# Probe-Scope_ADC_v1_0.net
KiCad netlist of a schematic drawn in Altium Designer
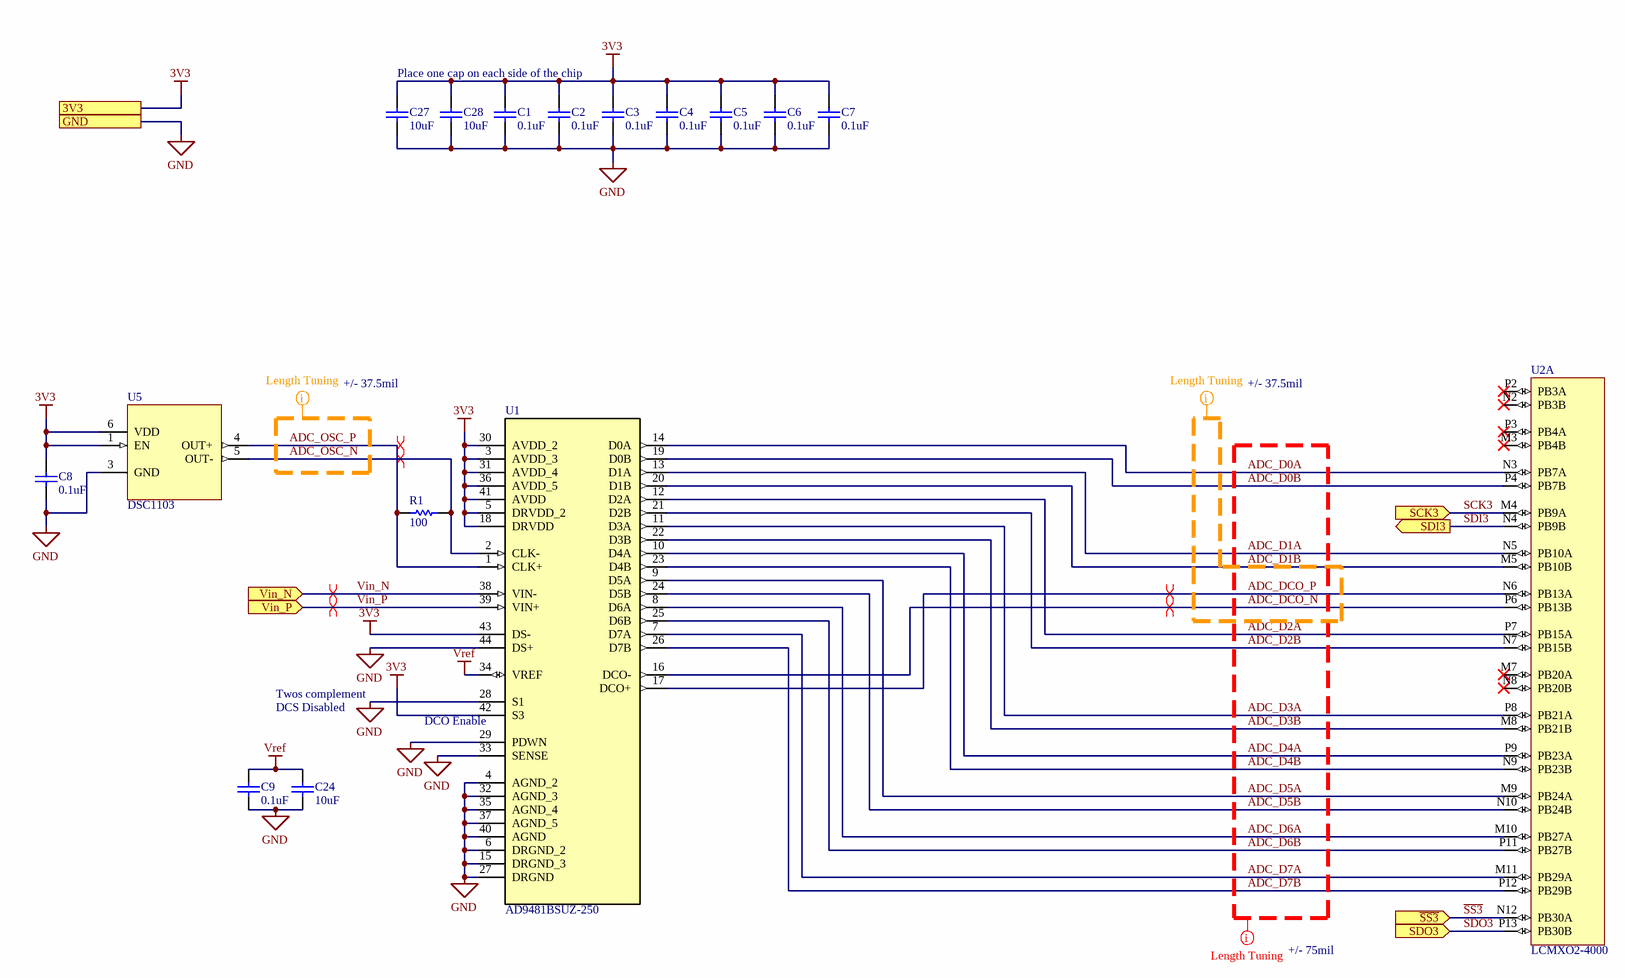
[diagram p0: Probe-Scope ADC v1.0.SchDoc]

(export (version "E")
  (design (tool "Eeschema 10.0.6"))
  (components
    (comp (ref "C1")
      (value "0.1uF")
      (footprint "0402(1005)")
      (fields
        (field (name "MANF") "Samsung Electro-Mechanics")
        (field (name "TOLERANCE") "10")
        (field (name "VOLTAGE") "6.3")
        (field (name "MODIFIED BY") "jrowley")
        (field (name "APPROVED") "False")
      )
      (libsource (lib "MENG Database Library VPN") (part "Cap"))
    )
    (comp (ref "C2")
      (value "0.1uF")
      (footprint "0402(1005)")
      (fields
        (field (name "MANF") "Samsung Electro-Mechanics")
        (field (name "TOLERANCE") "10")
        (field (name "VOLTAGE") "6.3")
        (field (name "MODIFIED BY") "jrowley")
        (field (name "APPROVED") "False")
      )
      (libsource (lib "MENG Database Library VPN") (part "Cap"))
    )
    (comp (ref "C3")
      (value "0.1uF")
      (footprint "0402(1005)")
      (fields
        (field (name "MANF") "Samsung Electro-Mechanics")
        (field (name "TOLERANCE") "10")
        (field (name "VOLTAGE") "6.3")
        (field (name "MODIFIED BY") "jrowley")
        (field (name "APPROVED") "False")
      )
      (libsource (lib "MENG Database Library VPN") (part "Cap"))
    )
    (comp (ref "C4")
      (value "0.1uF")
      (footprint "0402(1005)")
      (fields
        (field (name "MANF") "Samsung Electro-Mechanics")
        (field (name "TOLERANCE") "10")
        (field (name "VOLTAGE") "6.3")
        (field (name "MODIFIED BY") "jrowley")
        (field (name "APPROVED") "False")
      )
      (libsource (lib "MENG Database Library VPN") (part "Cap"))
    )
    (comp (ref "C5")
      (value "0.1uF")
      (footprint "0402(1005)")
      (fields
        (field (name "MANF") "Samsung Electro-Mechanics")
        (field (name "TOLERANCE") "10")
        (field (name "VOLTAGE") "6.3")
        (field (name "MODIFIED BY") "jrowley")
        (field (name "APPROVED") "False")
      )
      (libsource (lib "MENG Database Library VPN") (part "Cap"))
    )
    (comp (ref "C6")
      (value "0.1uF")
      (footprint "0402(1005)")
      (fields
        (field (name "MANF") "Samsung Electro-Mechanics")
        (field (name "TOLERANCE") "10")
        (field (name "VOLTAGE") "6.3")
        (field (name "MODIFIED BY") "jrowley")
        (field (name "APPROVED") "False")
      )
      (libsource (lib "MENG Database Library VPN") (part "Cap"))
    )
    (comp (ref "C7")
      (value "0.1uF")
      (footprint "0402(1005)")
      (fields
        (field (name "MANF") "Samsung Electro-Mechanics")
        (field (name "TOLERANCE") "10")
        (field (name "VOLTAGE") "6.3")
        (field (name "MODIFIED BY") "jrowley")
        (field (name "APPROVED") "False")
      )
      (libsource (lib "MENG Database Library VPN") (part "Cap"))
    )
    (comp (ref "C8")
      (value "0.1uF")
      (footprint "0402(1005)")
      (fields
        (field (name "MANF") "Samsung Electro-Mechanics")
        (field (name "TOLERANCE") "10")
        (field (name "VOLTAGE") "6.3")
        (field (name "MODIFIED BY") "jrowley")
        (field (name "APPROVED") "False")
      )
      (libsource (lib "MENG Database Library VPN") (part "Cap"))
    )
    (comp (ref "C9")
      (value "0.1uF")
      (footprint "0402(1005)")
      (fields
        (field (name "MANF") "Samsung Electro-Mechanics")
        (field (name "TOLERANCE") "10")
        (field (name "VOLTAGE") "6.3")
        (field (name "MODIFIED BY") "jrowley")
        (field (name "APPROVED") "False")
      )
      (libsource (lib "MENG Database Library VPN") (part "Cap"))
    )
    (comp (ref "C24")
      (value "10uF")
      (footprint "0603(1608)")
      (fields
        (field (name "MANF") "Samsung Electro-Mechanics")
        (field (name "TOLERANCE") "20")
        (field (name "VOLTAGE") "25")
        (field (name "MODIFIED BY") "sotterbacher")
        (field (name "APPROVED") "True")
      )
      (libsource (lib "MENG Database Library VPN") (part "Cap"))
    )
    (comp (ref "C27")
      (value "10uF")
      (footprint "0603(1608)")
      (fields
        (field (name "MANF") "Samsung Electro-Mechanics")
        (field (name "TOLERANCE") "20")
        (field (name "VOLTAGE") "25")
        (field (name "MODIFIED BY") "sotterbacher")
        (field (name "APPROVED") "True")
      )
      (libsource (lib "MENG Database Library VPN") (part "Cap"))
    )
    (comp (ref "C28")
      (value "10uF")
      (footprint "0603(1608)")
      (fields
        (field (name "MANF") "Samsung Electro-Mechanics")
        (field (name "TOLERANCE") "20")
        (field (name "VOLTAGE") "25")
        (field (name "MODIFIED BY") "sotterbacher")
        (field (name "APPROVED") "True")
      )
      (libsource (lib "MENG Database Library VPN") (part "Cap"))
    )
    (comp (ref "R1")
      (value "100")
      (footprint "0402(1005)")
      (fields
        (field (name "MANF") "Yageo")
        (field (name "TOLERANCE") "1")
        (field (name "POWER") "0.0625")
        (field (name "MODIFIED BY") "jrowley")
        (field (name "APPROVED") "False")
      )
      (libsource (lib "MENG Database Library VPN") (part "Res1"))
    )
    (comp (ref "U1")
      (value "AD9481BSUZ-250")
      (footprint "QFP80P1200X1200X120-44N")
      (description "Single ADC Pipelined 250Msps 8-bit Parallel/LVDS 44-Pin TQFP Tray")
      (fields (field (name "MANF") "Analog Devices Inc."))
      (libsource (lib "PS") (part "AD9481BSUZ-250"))
    )
    (comp (ref "U2")
      (value "LCMXO2-4000")
      (footprint "132_Ball_csBGA_MachXO2")
      (fields (field (name "MANF") "Lattice Semiconductor"))
      (libsource (lib "PS v1.0") (part "MachXO2-4000"))
    )
    (comp (ref "U5")
      (value "DSC1103")
      (footprint "MCHP_H5A")
      (fields (field (name "MANF") "Microchip Technology"))
      (libsource (lib "PS v1.0") (part "DSC1103"))
    )
  )
  (nets
    (net (code "1") (name "/ADC_D0A") (class "Default")
      (node (ref "U1") (pin "14") (pinfunction "D0A_14") (pintype "output"))
      (node (ref "U2") (pin "N3") (pinfunction "PB7A_N3") (pintype "bidirectional"))
    )
    (net (code "2") (name "/ADC_D0B") (class "Default")
      (node (ref "U1") (pin "19") (pinfunction "D0B_19") (pintype "output"))
      (node (ref "U2") (pin "P4") (pinfunction "PB7B_P4") (pintype "bidirectional"))
    )
    (net (code "3") (name "/ADC_D1A") (class "Default")
      (node (ref "U1") (pin "13") (pinfunction "D1A_13") (pintype "output"))
      (node (ref "U2") (pin "N5") (pinfunction "PB10A_N5") (pintype "bidirectional"))
    )
    (net (code "4") (name "/ADC_D1B") (class "Default")
      (node (ref "U1") (pin "20") (pinfunction "D1B_20") (pintype "output"))
      (node (ref "U2") (pin "M5") (pinfunction "PB10B_M5") (pintype "bidirectional"))
    )
    (net (code "5") (name "/ADC_D2A") (class "Default")
      (node (ref "U1") (pin "12") (pinfunction "D2A_12") (pintype "output"))
      (node (ref "U2") (pin "P7") (pinfunction "PB15A_P7") (pintype "bidirectional"))
    )
    (net (code "6") (name "/ADC_D2B") (class "Default")
      (node (ref "U1") (pin "21") (pinfunction "D2B_21") (pintype "output"))
      (node (ref "U2") (pin "N7") (pinfunction "PB15B_N7") (pintype "bidirectional"))
    )
    (net (code "7") (name "/ADC_D3A") (class "Default")
      (node (ref "U1") (pin "11") (pinfunction "D3A_11") (pintype "output"))
      (node (ref "U2") (pin "P8") (pinfunction "PB21A_P8") (pintype "bidirectional"))
    )
    (net (code "8") (name "/ADC_D3B") (class "Default")
      (node (ref "U1") (pin "22") (pinfunction "D3B_22") (pintype "output"))
      (node (ref "U2") (pin "M8") (pinfunction "PB21B_M8") (pintype "bidirectional"))
    )
    (net (code "9") (name "/ADC_D4A") (class "Default")
      (node (ref "U1") (pin "10") (pinfunction "D4A_10") (pintype "output"))
      (node (ref "U2") (pin "P9") (pinfunction "PB23A_P9") (pintype "bidirectional"))
    )
    (net (code "10") (name "/ADC_D4B") (class "Default")
      (node (ref "U1") (pin "23") (pinfunction "D4B_23") (pintype "output"))
      (node (ref "U2") (pin "N9") (pinfunction "PB23B_N9") (pintype "bidirectional"))
    )
    (net (code "11") (name "/ADC_D5A") (class "Default")
      (node (ref "U1") (pin "9") (pinfunction "D5A_9") (pintype "output"))
      (node (ref "U2") (pin "M9") (pinfunction "PB24A_M9") (pintype "bidirectional"))
    )
    (net (code "12") (name "/ADC_D5B") (class "Default")
      (node (ref "U1") (pin "24") (pinfunction "D5B_24") (pintype "output"))
      (node (ref "U2") (pin "N10") (pinfunction "PB24B_N10") (pintype "bidirectional"))
    )
    (net (code "13") (name "/ADC_D6A") (class "Default")
      (node (ref "U1") (pin "8") (pinfunction "D6A_8") (pintype "output"))
      (node (ref "U2") (pin "M10") (pinfunction "PB27A_M10") (pintype "bidirectional"))
    )
    (net (code "14") (name "/ADC_D6B") (class "Default")
      (node (ref "U1") (pin "25") (pinfunction "D6B_25") (pintype "output"))
      (node (ref "U2") (pin "P11") (pinfunction "PB27B_P11") (pintype "bidirectional"))
    )
    (net (code "15") (name "/ADC_D7A") (class "Default")
      (node (ref "U1") (pin "7") (pinfunction "D7A_7") (pintype "output"))
      (node (ref "U2") (pin "M11") (pinfunction "PB29A_M11") (pintype "bidirectional"))
    )
    (net (code "16") (name "/ADC_D7B") (class "Default")
      (node (ref "U1") (pin "26") (pinfunction "D7B_26") (pintype "output"))
      (node (ref "U2") (pin "P12") (pinfunction "PB29B_P12") (pintype "bidirectional"))
    )
    (net (code "17") (name "/ADC_DCO_N") (class "Default")
      (node (ref "U1") (pin "16") (pinfunction "DCO-_16") (pintype "output"))
      (node (ref "U2") (pin "P6") (pinfunction "PB13B_P6") (pintype "bidirectional"))
    )
    (net (code "18") (name "/ADC_DCO_P") (class "Default")
      (node (ref "U1") (pin "17") (pinfunction "DCO+_17") (pintype "output"))
      (node (ref "U2") (pin "N6") (pinfunction "PB13A_N6") (pintype "bidirectional"))
    )
    (net (code "19") (name "/ADC_OSC_N") (class "Default")
      (node (ref "R1") (pin "2") (pinfunction "2_2") (pintype "passive"))
      (node (ref "U1") (pin "2") (pinfunction "CLK-_2") (pintype "input"))
      (node (ref "U5") (pin "5") (pinfunction "OUT-_5") (pintype "output"))
    )
    (net (code "20") (name "/ADC_OSC_P") (class "Default")
      (node (ref "R1") (pin "1") (pinfunction "1_1") (pintype "passive"))
      (node (ref "U1") (pin "1") (pinfunction "CLK+_1") (pintype "input"))
      (node (ref "U5") (pin "4") (pinfunction "OUT+_4") (pintype "output"))
    )
    (net (code "21") (name "/SCK3") (class "Default")
      (node (ref "U2") (pin "M4") (pinfunction "PB9A_M4") (pintype "bidirectional"))
    )
    (net (code "22") (name "/SDI3") (class "Default")
      (node (ref "U2") (pin "N4") (pinfunction "PB9B_N4") (pintype "bidirectional"))
    )
    (net (code "23") (name "/SDO3") (class "Default")
      (node (ref "U2") (pin "P13") (pinfunction "PB30B_P13") (pintype "bidirectional"))
    )
    (net (code "24") (name "/Vin_N") (class "Default")
      (node (ref "U1") (pin "38") (pinfunction "VIN-_38") (pintype "input"))
    )
    (net (code "25") (name "/Vin_P") (class "Default")
      (node (ref "U1") (pin "39") (pinfunction "VIN+_39") (pintype "input"))
    )
    (net (code "26") (name "/~{SS3}") (class "Default")
      (node (ref "U2") (pin "N12") (pinfunction "PB30A_N12") (pintype "bidirectional"))
    )
    (net (code "27") (name "3V3") (class "Default")
      (node (ref "C1") (pin "2") (pinfunction "2_2") (pintype "passive"))
      (node (ref "C2") (pin "2") (pinfunction "2_2") (pintype "passive"))
      (node (ref "C27") (pin "2") (pinfunction "2_2") (pintype "passive"))
      (node (ref "C28") (pin "2") (pinfunction "2_2") (pintype "passive"))
      (node (ref "C3") (pin "2") (pinfunction "2_2") (pintype "passive"))
      (node (ref "C4") (pin "2") (pinfunction "2_2") (pintype "passive"))
      (node (ref "C5") (pin "2") (pinfunction "2_2") (pintype "passive"))
      (node (ref "C6") (pin "2") (pinfunction "2_2") (pintype "passive"))
      (node (ref "C7") (pin "2") (pinfunction "2_2") (pintype "passive"))
      (node (ref "C8") (pin "2") (pinfunction "2_2") (pintype "passive"))
      (node (ref "U1") (pin "18") (pinfunction "DRVDD_18") (pintype "power_in"))
      (node (ref "U1") (pin "3") (pinfunction "AVDD_3_3") (pintype "power_in"))
      (node (ref "U1") (pin "30") (pinfunction "AVDD_2_30") (pintype "power_in"))
      (node (ref "U1") (pin "31") (pinfunction "AVDD_4_31") (pintype "power_in"))
      (node (ref "U1") (pin "36") (pinfunction "AVDD_5_36") (pintype "power_in"))
      (node (ref "U1") (pin "41") (pinfunction "AVDD_41") (pintype "power_in"))
      (node (ref "U1") (pin "42") (pinfunction "S3_42") (pintype "passive"))
      (node (ref "U1") (pin "43") (pinfunction "DS-_43") (pintype "passive"))
      (node (ref "U1") (pin "5") (pinfunction "DRVDD_2_5") (pintype "power_in"))
      (node (ref "U5") (pin "1") (pinfunction "EN_1") (pintype "input"))
      (node (ref "U5") (pin "6") (pinfunction "VDD_6") (pintype "power_in"))
    )
    (net (code "28") (name "GND") (class "Default")
      (node (ref "C1") (pin "1") (pinfunction "1_1") (pintype "passive"))
      (node (ref "C2") (pin "1") (pinfunction "1_1") (pintype "passive"))
      (node (ref "C24") (pin "1") (pinfunction "1_1") (pintype "passive"))
      (node (ref "C27") (pin "1") (pinfunction "1_1") (pintype "passive"))
      (node (ref "C28") (pin "1") (pinfunction "1_1") (pintype "passive"))
      (node (ref "C3") (pin "1") (pinfunction "1_1") (pintype "passive"))
      (node (ref "C4") (pin "1") (pinfunction "1_1") (pintype "passive"))
      (node (ref "C5") (pin "1") (pinfunction "1_1") (pintype "passive"))
      (node (ref "C6") (pin "1") (pinfunction "1_1") (pintype "passive"))
      (node (ref "C7") (pin "1") (pinfunction "1_1") (pintype "passive"))
      (node (ref "C8") (pin "1") (pinfunction "1_1") (pintype "passive"))
      (node (ref "C9") (pin "1") (pinfunction "1_1") (pintype "passive"))
      (node (ref "U1") (pin "15") (pinfunction "DRGND_3_15") (pintype "passive"))
      (node (ref "U1") (pin "27") (pinfunction "DRGND_27") (pintype "passive"))
      (node (ref "U1") (pin "28") (pinfunction "S1_28") (pintype "passive"))
      (node (ref "U1") (pin "29") (pinfunction "PDWN_29") (pintype "passive"))
      (node (ref "U1") (pin "32") (pinfunction "AGND_3_32") (pintype "passive"))
      (node (ref "U1") (pin "33") (pinfunction "SENSE_33") (pintype "passive"))
      (node (ref "U1") (pin "35") (pinfunction "AGND_4_35") (pintype "passive"))
      (node (ref "U1") (pin "37") (pinfunction "AGND_5_37") (pintype "passive"))
      (node (ref "U1") (pin "4") (pinfunction "AGND_2_4") (pintype "passive"))
      (node (ref "U1") (pin "40") (pinfunction "AGND_40") (pintype "passive"))
      (node (ref "U1") (pin "44") (pinfunction "DS+_44") (pintype "passive"))
      (node (ref "U1") (pin "6") (pinfunction "DRGND_2_6") (pintype "passive"))
      (node (ref "U5") (pin "3") (pinfunction "GND_3") (pintype "power_in"))
    )
    (net (code "29") (name "Vref") (class "Default")
      (node (ref "C24") (pin "2") (pinfunction "2_2") (pintype "passive"))
      (node (ref "C9") (pin "2") (pinfunction "2_2") (pintype "passive"))
      (node (ref "U1") (pin "34") (pinfunction "VREF_34") (pintype "bidirectional"))
    )
    (net (code "30") (name "unconnected-(U2A-PB3A-PadP2)") (class "Default")
      (node (ref "U2") (pin "P2") (pinfunction "PB3A_P2") (pintype "bidirectional+no_connect"))
    )
    (net (code "31") (name "unconnected-(U2A-PB3B-PadN2)") (class "Default")
      (node (ref "U2") (pin "N2") (pinfunction "PB3B_N2") (pintype "bidirectional+no_connect"))
    )
    (net (code "32") (name "unconnected-(U2A-PB4A-PadP3)") (class "Default")
      (node (ref "U2") (pin "P3") (pinfunction "PB4A_P3") (pintype "bidirectional+no_connect"))
    )
    (net (code "33") (name "unconnected-(U2A-PB4B-PadM3)") (class "Default")
      (node (ref "U2") (pin "M3") (pinfunction "PB4B_M3") (pintype "bidirectional+no_connect"))
    )
    (net (code "34") (name "unconnected-(U2A-PB20A-PadM7)") (class "Default")
      (node (ref "U2") (pin "M7") (pinfunction "PB20A_M7") (pintype "bidirectional+no_connect"))
    )
    (net (code "35") (name "unconnected-(U2A-PB20B-PadN8)") (class "Default")
      (node (ref "U2") (pin "N8") (pinfunction "PB20B_N8") (pintype "bidirectional+no_connect"))
    )
  )
)
